# DS18B20_Modbus_v0_1.net
KiCad netlist of a schematic drawn in EAGLE
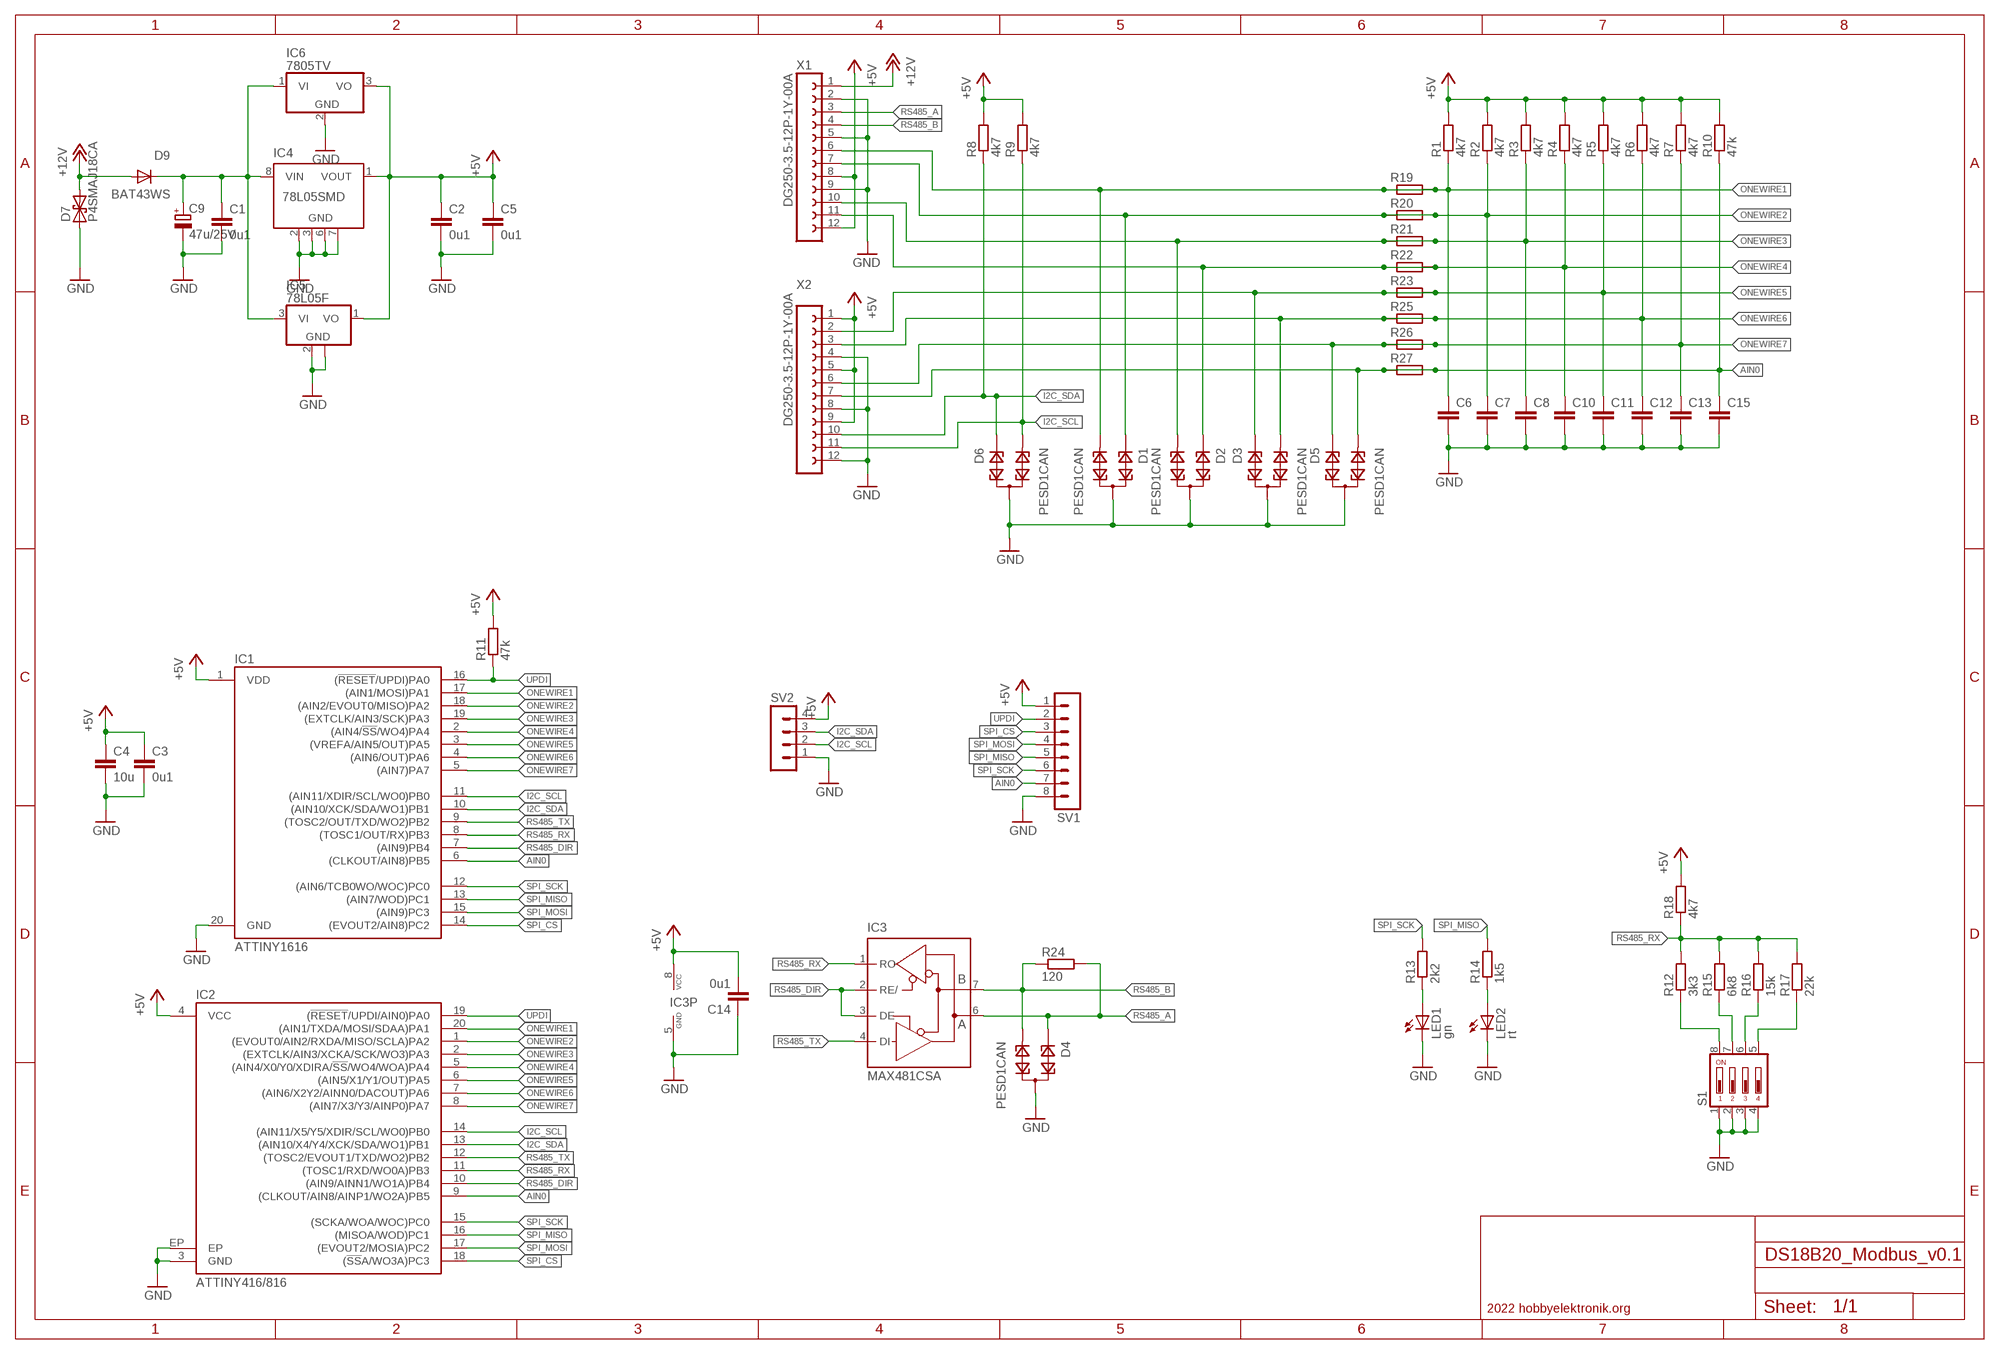
[diagram p0: schematic, sheet 1]

(export (version "E")
  (design (tool "Eeschema 10.0.6"))
  (components
    (comp (ref "C1")
      (value "0u1")
      (footprint "eagle-import:C0805")
      (libsource (lib "eagle-import") (part "C-EUC0805"))
    )
    (comp (ref "C2")
      (value "0u1")
      (footprint "eagle-import:C0603")
      (libsource (lib "eagle-import") (part "C-EUC0603"))
    )
    (comp (ref "C3")
      (value "0u1")
      (footprint "eagle-import:C0603")
      (libsource (lib "eagle-import") (part "C-EUC0603"))
    )
    (comp (ref "C4")
      (value "10u")
      (footprint "eagle-import:C0805")
      (libsource (lib "eagle-import") (part "C-EUC0805"))
    )
    (comp (ref "C5")
      (value "0u1")
      (footprint "eagle-import:C0603")
      (libsource (lib "eagle-import") (part "C-EUC0603"))
    )
    (comp (ref "C6")
      (value "C-EUC0603")
      (footprint "eagle-import:C0603")
      (libsource (lib "eagle-import") (part "C-EUC0603"))
    )
    (comp (ref "C7")
      (value "C-EUC0603")
      (footprint "eagle-import:C0603")
      (libsource (lib "eagle-import") (part "C-EUC0603"))
    )
    (comp (ref "C8")
      (value "C-EUC0603")
      (footprint "eagle-import:C0603")
      (libsource (lib "eagle-import") (part "C-EUC0603"))
    )
    (comp (ref "C9")
      (value "47u/25V")
      (footprint "eagle-import:E2,5-5")
      (libsource (lib "eagle-import") (part "CPOL-EUE2.5-5"))
    )
    (comp (ref "C10")
      (value "C-EUC0603")
      (footprint "eagle-import:C0603")
      (libsource (lib "eagle-import") (part "C-EUC0603"))
    )
    (comp (ref "C11")
      (value "C-EUC0603")
      (footprint "eagle-import:C0603")
      (libsource (lib "eagle-import") (part "C-EUC0603"))
    )
    (comp (ref "C12")
      (value "C-EUC0603")
      (footprint "eagle-import:C0603")
      (libsource (lib "eagle-import") (part "C-EUC0603"))
    )
    (comp (ref "C13")
      (value "C-EUC0603")
      (footprint "eagle-import:C0603")
      (libsource (lib "eagle-import") (part "C-EUC0603"))
    )
    (comp (ref "C14")
      (value "0u1")
      (footprint "eagle-import:C0603")
      (libsource (lib "eagle-import") (part "C-EUC0603"))
    )
    (comp (ref "C15")
      (value "C-EUC0603")
      (footprint "eagle-import:C0603")
      (libsource (lib "eagle-import") (part "C-EUC0603"))
    )
    (comp (ref "D1")
      (value "PESD1CAN")
      (footprint "eagle-import:SOT23")
      (libsource (lib "eagle-import") (part "PESD1CAN"))
    )
    (comp (ref "D2")
      (value "PESD1CAN")
      (footprint "eagle-import:SOT23")
      (libsource (lib "eagle-import") (part "PESD1CAN"))
    )
    (comp (ref "D3")
      (value "PESD1CAN")
      (footprint "eagle-import:SOT23")
      (libsource (lib "eagle-import") (part "PESD1CAN"))
    )
    (comp (ref "D4")
      (value "PESD1CAN")
      (footprint "eagle-import:SOT23")
      (libsource (lib "eagle-import") (part "PESD1CAN"))
    )
    (comp (ref "D5")
      (value "PESD1CAN")
      (footprint "eagle-import:SOT23")
      (libsource (lib "eagle-import") (part "PESD1CAN"))
    )
    (comp (ref "D6")
      (value "PESD1CAN")
      (footprint "eagle-import:SOT23")
      (libsource (lib "eagle-import") (part "PESD1CAN"))
    )
    (comp (ref "D7")
      (value "P4SMAJ18CA")
      (footprint "eagle-import:DO214AC")
      (fields (field (name "OC_REICHELT") "P4SMAJ18CA"))
      (libsource (lib "eagle-import") (part "P4SMAJ10CA"))
    )
    (comp (ref "D9")
      (value "BAT43WS")
      (footprint "eagle-import:SOD323-W")
      (libsource (lib "eagle-import") (part "DIODE-SOD323-W"))
    )
    (comp (ref "IC1")
      (value "ATTINY1616")
      (footprint "eagle-import:SO20_T1616")
      (libsource (lib "eagle-import") (part "ATTINY1616"))
    )
    (comp (ref "IC2")
      (value "ATTINY416/816")
      (footprint "eagle-import:ZCL_VQFN-20")
      (libsource (lib "eagle-import") (part "ATTINY416/816"))
    )
    (comp (ref "IC3")
      (value "MAX481CSA")
      (footprint "eagle-import:SO08")
      (fields (field (name "MF") "MAXIM") (field (name "OC_REICHELT") "MAX 481 CSA"))
      (libsource (lib "eagle-import") (part "MAX481CSA"))
    )
    (comp (ref "IC4")
      (value "78L05SMD")
      (footprint "eagle-import:SO08")
      (libsource (lib "eagle-import") (part "78LSMD05"))
    )
    (comp (ref "IC5")
      (value "78L05F")
      (footprint "eagle-import:SOT89")
      (libsource (lib "eagle-import") (part "78LF05"))
    )
    (comp (ref "IC6")
      (value "7805TV")
      (footprint "eagle-import:TO220V")
      (libsource (lib "eagle-import") (part "78TV05"))
    )
    (comp (ref "LED1")
      (value "gn")
      (footprint "eagle-import:SML0805")
      (libsource (lib "eagle-import") (part "LEDSML0805"))
    )
    (comp (ref "LED2")
      (value "rt")
      (footprint "eagle-import:SML0805")
      (libsource (lib "eagle-import") (part "LEDSML0805"))
    )
    (comp (ref "R1")
      (value "4k7")
      (footprint "eagle-import:R0603")
      (libsource (lib "eagle-import") (part "R-EU_R0603"))
    )
    (comp (ref "R2")
      (value "4k7")
      (footprint "eagle-import:R0603")
      (libsource (lib "eagle-import") (part "R-EU_R0603"))
    )
    (comp (ref "R3")
      (value "4k7")
      (footprint "eagle-import:R0603")
      (libsource (lib "eagle-import") (part "R-EU_R0603"))
    )
    (comp (ref "R4")
      (value "4k7")
      (footprint "eagle-import:R0603")
      (libsource (lib "eagle-import") (part "R-EU_R0603"))
    )
    (comp (ref "R5")
      (value "4k7")
      (footprint "eagle-import:R0603")
      (libsource (lib "eagle-import") (part "R-EU_R0603"))
    )
    (comp (ref "R6")
      (value "4k7")
      (footprint "eagle-import:R0603")
      (libsource (lib "eagle-import") (part "R-EU_R0603"))
    )
    (comp (ref "R7")
      (value "4k7")
      (footprint "eagle-import:R0603")
      (libsource (lib "eagle-import") (part "R-EU_R0603"))
    )
    (comp (ref "R8")
      (value "4k7")
      (footprint "eagle-import:R0603")
      (libsource (lib "eagle-import") (part "R-EU_R0603"))
    )
    (comp (ref "R9")
      (value "4k7")
      (footprint "eagle-import:R0603")
      (libsource (lib "eagle-import") (part "R-EU_R0603"))
    )
    (comp (ref "R10")
      (value "47k")
      (footprint "eagle-import:R0603")
      (libsource (lib "eagle-import") (part "R-EU_R0603"))
    )
    (comp (ref "R11")
      (value "47k")
      (footprint "eagle-import:R0603")
      (libsource (lib "eagle-import") (part "R-EU_R0603"))
    )
    (comp (ref "R12")
      (value "3k3")
      (footprint "eagle-import:R0603")
      (libsource (lib "eagle-import") (part "R-EU_R0603"))
    )
    (comp (ref "R13")
      (value "2k2")
      (footprint "eagle-import:R0603")
      (libsource (lib "eagle-import") (part "R-EU_R0603"))
    )
    (comp (ref "R14")
      (value "1k5")
      (footprint "eagle-import:R0603")
      (libsource (lib "eagle-import") (part "R-EU_R0603"))
    )
    (comp (ref "R15")
      (value "6k8")
      (footprint "eagle-import:R0603")
      (libsource (lib "eagle-import") (part "R-EU_R0603"))
    )
    (comp (ref "R16")
      (value "15k")
      (footprint "eagle-import:R0603")
      (libsource (lib "eagle-import") (part "R-EU_R0603"))
    )
    (comp (ref "R17")
      (value "22k")
      (footprint "eagle-import:R0603")
      (libsource (lib "eagle-import") (part "R-EU_R0603"))
    )
    (comp (ref "R18")
      (value "4k7")
      (footprint "eagle-import:R0603")
      (libsource (lib "eagle-import") (part "R-EU_R0603"))
    )
    (comp (ref "R19")
      (value "R-EU_R0603")
      (footprint "eagle-import:R0603")
      (libsource (lib "eagle-import") (part "R-EU_R0603"))
    )
    (comp (ref "R20")
      (value "R-EU_R0603")
      (footprint "eagle-import:R0603")
      (libsource (lib "eagle-import") (part "R-EU_R0603"))
    )
    (comp (ref "R21")
      (value "R-EU_R0603")
      (footprint "eagle-import:R0603")
      (libsource (lib "eagle-import") (part "R-EU_R0603"))
    )
    (comp (ref "R22")
      (value "R-EU_R0603")
      (footprint "eagle-import:R0603")
      (libsource (lib "eagle-import") (part "R-EU_R0603"))
    )
    (comp (ref "R23")
      (value "R-EU_R0603")
      (footprint "eagle-import:R0603")
      (libsource (lib "eagle-import") (part "R-EU_R0603"))
    )
    (comp (ref "R24")
      (value "120")
      (footprint "eagle-import:R0603")
      (libsource (lib "eagle-import") (part "R-EU_R0603"))
    )
    (comp (ref "R25")
      (value "R-EU_R0603")
      (footprint "eagle-import:R0603")
      (libsource (lib "eagle-import") (part "R-EU_R0603"))
    )
    (comp (ref "R26")
      (value "R-EU_R0603")
      (footprint "eagle-import:R0603")
      (libsource (lib "eagle-import") (part "R-EU_R0603"))
    )
    (comp (ref "R27")
      (value "R-EU_R0603")
      (footprint "eagle-import:R0603")
      (libsource (lib "eagle-import") (part "R-EU_R0603"))
    )
    (comp (ref "S1")
      (value "DS04")
      (footprint "eagle-import:DS-04")
      (libsource (lib "eagle-import") (part "DS04"))
    )
    (comp (ref "SV1")
      (value "MA08-1R")
      (footprint "eagle-import:MA08-1R")
      (libsource (lib "eagle-import") (part "MA08-1R"))
    )
    (comp (ref "SV2")
      (value "MA04-1R")
      (footprint "eagle-import:MA04-1R")
      (libsource (lib "eagle-import") (part "MA04-1R"))
    )
    (comp (ref "X1")
      (value "DG250-3.5-12P-1Y-00A")
      (footprint "eagle-import:DG250-3.5-12P-1Y-00A")
      (libsource (lib "eagle-import") (part "DG250-3.5-12P-1Y-00A"))
    )
    (comp (ref "X2")
      (value "DG250-3.5-12P-1Y-00A")
      (footprint "eagle-import:DG250-3.5-12P-1Y-00A")
      (libsource (lib "eagle-import") (part "DG250-3.5-12P-1Y-00A"))
    )
  )
  (nets
    (net (code "1") (name "+5V") (class "Default")
      (node (ref "C14") (pin "2") (pinfunction "2_2") (pintype "passive"))
      (node (ref "C2") (pin "1") (pinfunction "1_1") (pintype "passive"))
      (node (ref "C3") (pin "1") (pinfunction "1_1") (pintype "passive"))
      (node (ref "C4") (pin "1") (pinfunction "1_1") (pintype "passive"))
      (node (ref "C5") (pin "1") (pinfunction "1_1") (pintype "passive"))
      (node (ref "IC1") (pin "1") (pinfunction "VDD_1") (pintype "power_in"))
      (node (ref "IC2") (pin "4") (pinfunction "VCC_4") (pintype "power_in"))
      (node (ref "IC3") (pin "8") (pinfunction "VCC_8") (pintype "power_in"))
      (node (ref "IC4") (pin "1") (pinfunction "VOUT_1") (pintype "output"))
      (node (ref "IC5") (pin "1") (pinfunction "VO_1") (pintype "passive"))
      (node (ref "IC6") (pin "3") (pinfunction "VO_3") (pintype "passive"))
      (node (ref "R1") (pin "2") (pinfunction "2_2") (pintype "passive"))
      (node (ref "R10") (pin "2") (pinfunction "2_2") (pintype "passive"))
      (node (ref "R11") (pin "2") (pinfunction "2_2") (pintype "passive"))
      (node (ref "R18") (pin "2") (pinfunction "2_2") (pintype "passive"))
      (node (ref "R2") (pin "2") (pinfunction "2_2") (pintype "passive"))
      (node (ref "R3") (pin "2") (pinfunction "2_2") (pintype "passive"))
      (node (ref "R4") (pin "2") (pinfunction "2_2") (pintype "passive"))
      (node (ref "R5") (pin "2") (pinfunction "2_2") (pintype "passive"))
      (node (ref "R6") (pin "2") (pinfunction "2_2") (pintype "passive"))
      (node (ref "R7") (pin "2") (pinfunction "2_2") (pintype "passive"))
      (node (ref "R8") (pin "2") (pinfunction "2_2") (pintype "passive"))
      (node (ref "R9") (pin "2") (pinfunction "2_2") (pintype "passive"))
      (node (ref "SV1") (pin "1") (pinfunction "1_1") (pintype "passive"))
      (node (ref "SV2") (pin "4") (pinfunction "4_4") (pintype "passive"))
      (node (ref "X1") (pin "12") (pinfunction "12_12") (pintype "passive"))
      (node (ref "X1") (pin "8") (pinfunction "8_8") (pintype "passive"))
      (node (ref "X2") (pin "1") (pinfunction "1_1") (pintype "passive"))
      (node (ref "X2") (pin "5") (pinfunction "5_5") (pintype "passive"))
      (node (ref "X2") (pin "9") (pinfunction "9_9") (pintype "passive"))
    )
    (net (code "2") (name "+12V") (class "Default")
      (node (ref "D7") (pin "2") (pinfunction "2_2") (pintype "passive"))
      (node (ref "D9") (pin "A") (pinfunction "A_A") (pintype "passive"))
      (node (ref "X1") (pin "1") (pinfunction "1_1") (pintype "passive"))
    )
    (net (code "3") (name "AIN0") (class "Default")
      (node (ref "C15") (pin "1") (pinfunction "1_1") (pintype "passive"))
      (node (ref "D5") (pin "2") (pinfunction "2_2") (pintype "passive"))
      (node (ref "IC1") (pin "6") (pinfunction "(CLKOUT/AIN8)PB5_6") (pintype "bidirectional"))
      (node (ref "IC2") (pin "9") (pinfunction "(CLKOUT/AIN8/AINP1/WO2A)PB5_9") (pintype "bidirectional"))
      (node (ref "R10") (pin "1") (pinfunction "1_1") (pintype "passive"))
      (node (ref "R27") (pin "1") (pinfunction "1_1") (pintype "passive"))
      (node (ref "R27") (pin "2") (pinfunction "2_2") (pintype "passive"))
      (node (ref "SV1") (pin "7") (pinfunction "7_7") (pintype "passive"))
      (node (ref "X2") (pin "7") (pinfunction "7_7") (pintype "passive"))
    )
    (net (code "4") (name "GND") (class "Default")
      (node (ref "C1") (pin "2") (pinfunction "2_2") (pintype "passive"))
      (node (ref "C10") (pin "2") (pinfunction "2_2") (pintype "passive"))
      (node (ref "C11") (pin "2") (pinfunction "2_2") (pintype "passive"))
      (node (ref "C12") (pin "2") (pinfunction "2_2") (pintype "passive"))
      (node (ref "C13") (pin "2") (pinfunction "2_2") (pintype "passive"))
      (node (ref "C14") (pin "1") (pinfunction "1_1") (pintype "passive"))
      (node (ref "C15") (pin "2") (pinfunction "2_2") (pintype "passive"))
      (node (ref "C2") (pin "2") (pinfunction "2_2") (pintype "passive"))
      (node (ref "C3") (pin "2") (pinfunction "2_2") (pintype "passive"))
      (node (ref "C4") (pin "2") (pinfunction "2_2") (pintype "passive"))
      (node (ref "C5") (pin "2") (pinfunction "2_2") (pintype "passive"))
      (node (ref "C6") (pin "2") (pinfunction "2_2") (pintype "passive"))
      (node (ref "C7") (pin "2") (pinfunction "2_2") (pintype "passive"))
      (node (ref "C8") (pin "2") (pinfunction "2_2") (pintype "passive"))
      (node (ref "C9") (pin "-") (pinfunction "-_-") (pintype "passive"))
      (node (ref "D1") (pin "3") (pinfunction "3_3") (pintype "passive"))
      (node (ref "D2") (pin "3") (pinfunction "3_3") (pintype "passive"))
      (node (ref "D3") (pin "3") (pinfunction "3_3") (pintype "passive"))
      (node (ref "D4") (pin "3") (pinfunction "3_3") (pintype "passive"))
      (node (ref "D5") (pin "3") (pinfunction "3_3") (pintype "passive"))
      (node (ref "D6") (pin "3") (pinfunction "3_3") (pintype "passive"))
      (node (ref "D7") (pin "1") (pinfunction "1_1") (pintype "passive"))
      (node (ref "IC1") (pin "20") (pinfunction "GND_20") (pintype "power_in"))
      (node (ref "IC2") (pin "3") (pinfunction "GND_3") (pintype "power_in"))
      (node (ref "IC2") (pin "EP") (pinfunction "EP_EP") (pintype "power_in"))
      (node (ref "IC3") (pin "5") (pinfunction "GND_5") (pintype "power_in"))
      (node (ref "IC4") (pin "2") (pinfunction "GND_2") (pintype "power_in"))
      (node (ref "IC4") (pin "3") (pinfunction "GND_3") (pintype "power_in"))
      (node (ref "IC4") (pin "6") (pinfunction "GND_6") (pintype "power_in"))
      (node (ref "IC4") (pin "7") (pinfunction "GND_7") (pintype "power_in"))
      (node (ref "IC5") (pin "2") (pinfunction "GND_2") (pintype "passive"))
      (node (ref "IC5") (pin "2@1") (pinfunction "GND_2@1") (pintype "passive"))
      (node (ref "IC6") (pin "2") (pinfunction "GND_2") (pintype "passive"))
      (node (ref "LED1") (pin "C") (pinfunction "C_C") (pintype "passive"))
      (node (ref "LED2") (pin "C") (pinfunction "C_C") (pintype "passive"))
      (node (ref "S1") (pin "1") (pinfunction "1_1") (pintype "passive"))
      (node (ref "S1") (pin "2") (pinfunction "2_2") (pintype "passive"))
      (node (ref "S1") (pin "3") (pinfunction "3_3") (pintype "passive"))
      (node (ref "S1") (pin "4") (pinfunction "4_4") (pintype "passive"))
      (node (ref "SV1") (pin "8") (pinfunction "8_8") (pintype "passive"))
      (node (ref "SV2") (pin "1") (pinfunction "1_1") (pintype "passive"))
      (node (ref "X1") (pin "2") (pinfunction "2_2") (pintype "passive"))
      (node (ref "X1") (pin "5") (pinfunction "5_5") (pintype "passive"))
      (node (ref "X1") (pin "9") (pinfunction "9_9") (pintype "passive"))
      (node (ref "X2") (pin "12") (pinfunction "12_12") (pintype "passive"))
      (node (ref "X2") (pin "4") (pinfunction "4_4") (pintype "passive"))
      (node (ref "X2") (pin "8") (pinfunction "8_8") (pintype "passive"))
    )
    (net (code "5") (name "I2C_SCL") (class "Default")
      (node (ref "D6") (pin "2") (pinfunction "2_2") (pintype "passive"))
      (node (ref "IC1") (pin "11") (pinfunction "(AIN11/XDIR/SCL/WO0)PB0_11") (pintype "bidirectional"))
      (node (ref "IC2") (pin "14") (pinfunction "(AIN11/X5/Y5/XDIR/SCL/WO0)PB0_14") (pintype "bidirectional"))
      (node (ref "R9") (pin "1") (pinfunction "1_1") (pintype "passive"))
      (node (ref "SV2") (pin "2") (pinfunction "2_2") (pintype "passive"))
      (node (ref "X2") (pin "11") (pinfunction "11_11") (pintype "passive"))
    )
    (net (code "6") (name "I2C_SDA") (class "Default")
      (node (ref "D6") (pin "1") (pinfunction "1_1") (pintype "passive"))
      (node (ref "IC1") (pin "10") (pinfunction "(AIN10/XCK/SDA/WO1)PB1_10") (pintype "bidirectional"))
      (node (ref "IC2") (pin "13") (pinfunction "(AIN10/X4/Y4/XCK/SDA/WO1)PB1_13") (pintype "bidirectional"))
      (node (ref "R8") (pin "1") (pinfunction "1_1") (pintype "passive"))
      (node (ref "SV2") (pin "3") (pinfunction "3_3") (pintype "passive"))
      (node (ref "X2") (pin "10") (pinfunction "10_10") (pintype "passive"))
    )
    (net (code "7") (name "Net-(IC4A-VIN)") (class "Default")
      (node (ref "C1") (pin "1") (pinfunction "1_1") (pintype "passive"))
      (node (ref "C9") (pin "+") (pinfunction "+_+") (pintype "passive"))
      (node (ref "D9") (pin "C") (pinfunction "C_C") (pintype "passive"))
      (node (ref "IC4") (pin "8") (pinfunction "VIN_8") (pintype "passive"))
      (node (ref "IC5") (pin "3") (pinfunction "VI_3") (pintype "input"))
      (node (ref "IC6") (pin "1") (pinfunction "VI_1") (pintype "input"))
    )
    (net (code "8") (name "Net-(LED1-PadA)") (class "Default")
      (node (ref "LED1") (pin "A") (pinfunction "A_A") (pintype "passive"))
      (node (ref "R13") (pin "1") (pinfunction "1_1") (pintype "passive"))
    )
    (net (code "9") (name "Net-(LED2-PadA)") (class "Default")
      (node (ref "LED2") (pin "A") (pinfunction "A_A") (pintype "passive"))
      (node (ref "R14") (pin "1") (pinfunction "1_1") (pintype "passive"))
    )
    (net (code "10") (name "Net-(R12-Pad1)") (class "Default")
      (node (ref "R12") (pin "1") (pinfunction "1_1") (pintype "passive"))
      (node (ref "S1") (pin "8") (pinfunction "8_8") (pintype "passive"))
    )
    (net (code "11") (name "Net-(R15-Pad1)") (class "Default")
      (node (ref "R15") (pin "1") (pinfunction "1_1") (pintype "passive"))
      (node (ref "S1") (pin "7") (pinfunction "7_7") (pintype "passive"))
    )
    (net (code "12") (name "Net-(R16-Pad1)") (class "Default")
      (node (ref "R16") (pin "1") (pinfunction "1_1") (pintype "passive"))
      (node (ref "S1") (pin "6") (pinfunction "6_6") (pintype "passive"))
    )
    (net (code "13") (name "Net-(R17-Pad1)") (class "Default")
      (node (ref "R17") (pin "1") (pinfunction "1_1") (pintype "passive"))
      (node (ref "S1") (pin "5") (pinfunction "5_5") (pintype "passive"))
    )
    (net (code "14") (name "ONEWIRE1") (class "Default")
      (node (ref "C6") (pin "1") (pinfunction "1_1") (pintype "passive"))
      (node (ref "D1") (pin "2") (pinfunction "2_2") (pintype "passive"))
      (node (ref "IC1") (pin "17") (pinfunction "(AIN1/MOSI)PA1_17") (pintype "bidirectional"))
      (node (ref "IC2") (pin "20") (pinfunction "(AIN1/TXDA/MOSI/SDAA)PA1_20") (pintype "bidirectional"))
      (node (ref "R1") (pin "1") (pinfunction "1_1") (pintype "passive"))
      (node (ref "R19") (pin "1") (pinfunction "1_1") (pintype "passive"))
      (node (ref "R19") (pin "2") (pinfunction "2_2") (pintype "passive"))
      (node (ref "X1") (pin "6") (pinfunction "6_6") (pintype "passive"))
    )
    (net (code "15") (name "ONEWIRE2") (class "Default")
      (node (ref "C7") (pin "1") (pinfunction "1_1") (pintype "passive"))
      (node (ref "D1") (pin "1") (pinfunction "1_1") (pintype "passive"))
      (node (ref "IC1") (pin "18") (pinfunction "(AIN2/EVOUT0/MISO)PA2_18") (pintype "bidirectional"))
      (node (ref "IC2") (pin "1") (pinfunction "(EVOUT0/AIN2/RXDA/MISO/SCLA)PA2_1") (pintype "bidirectional"))
      (node (ref "R2") (pin "1") (pinfunction "1_1") (pintype "passive"))
      (node (ref "R20") (pin "1") (pinfunction "1_1") (pintype "passive"))
      (node (ref "R20") (pin "2") (pinfunction "2_2") (pintype "passive"))
      (node (ref "X1") (pin "7") (pinfunction "7_7") (pintype "passive"))
    )
    (net (code "16") (name "ONEWIRE3") (class "Default")
      (node (ref "C8") (pin "1") (pinfunction "1_1") (pintype "passive"))
      (node (ref "D2") (pin "2") (pinfunction "2_2") (pintype "passive"))
      (node (ref "IC1") (pin "19") (pinfunction "(EXTCLK/AIN3/SCK)PA3_19") (pintype "bidirectional"))
      (node (ref "IC2") (pin "2") (pinfunction "(EXTCLK/AIN3/XCKA/SCK/WO3)PA3_2") (pintype "bidirectional"))
      (node (ref "R21") (pin "1") (pinfunction "1_1") (pintype "passive"))
      (node (ref "R21") (pin "2") (pinfunction "2_2") (pintype "passive"))
      (node (ref "R3") (pin "1") (pinfunction "1_1") (pintype "passive"))
      (node (ref "X1") (pin "10") (pinfunction "10_10") (pintype "passive"))
    )
    (net (code "17") (name "ONEWIRE4") (class "Default")
      (node (ref "C10") (pin "1") (pinfunction "1_1") (pintype "passive"))
      (node (ref "D2") (pin "1") (pinfunction "1_1") (pintype "passive"))
      (node (ref "IC1") (pin "2") (pinfunction "(AIN4/~{SS}/WO4)PA4_2") (pintype "bidirectional"))
      (node (ref "IC2") (pin "5") (pinfunction "(AIN4/X0/Y0/XDIRA/~{SS}/WO4/WOA)PA4_5") (pintype "bidirectional"))
      (node (ref "R22") (pin "1") (pinfunction "1_1") (pintype "passive"))
      (node (ref "R22") (pin "2") (pinfunction "2_2") (pintype "passive"))
      (node (ref "R4") (pin "1") (pinfunction "1_1") (pintype "passive"))
      (node (ref "X1") (pin "11") (pinfunction "11_11") (pintype "passive"))
    )
    (net (code "18") (name "ONEWIRE5") (class "Default")
      (node (ref "C11") (pin "1") (pinfunction "1_1") (pintype "passive"))
      (node (ref "D3") (pin "1") (pinfunction "1_1") (pintype "passive"))
      (node (ref "IC1") (pin "3") (pinfunction "(VREFA/AIN5/OUT)PA5_3") (pintype "bidirectional"))
      (node (ref "IC2") (pin "6") (pinfunction "(AIN5/X1/Y1/OUT)PA5_6") (pintype "bidirectional"))
      (node (ref "R23") (pin "1") (pinfunction "1_1") (pintype "passive"))
      (node (ref "R23") (pin "2") (pinfunction "2_2") (pintype "passive"))
      (node (ref "R5") (pin "1") (pinfunction "1_1") (pintype "passive"))
      (node (ref "X2") (pin "2") (pinfunction "2_2") (pintype "passive"))
    )
    (net (code "19") (name "ONEWIRE6") (class "Default")
      (node (ref "C12") (pin "1") (pinfunction "1_1") (pintype "passive"))
      (node (ref "D3") (pin "2") (pinfunction "2_2") (pintype "passive"))
      (node (ref "IC1") (pin "4") (pinfunction "(AIN6/OUT)PA6_4") (pintype "bidirectional"))
      (node (ref "IC2") (pin "7") (pinfunction "(AIN6/X2Y2/AINN0/DACOUT)PA6_7") (pintype "bidirectional"))
      (node (ref "R25") (pin "1") (pinfunction "1_1") (pintype "passive"))
      (node (ref "R25") (pin "2") (pinfunction "2_2") (pintype "passive"))
      (node (ref "R6") (pin "1") (pinfunction "1_1") (pintype "passive"))
      (node (ref "X2") (pin "3") (pinfunction "3_3") (pintype "passive"))
    )
    (net (code "20") (name "ONEWIRE7") (class "Default")
      (node (ref "C13") (pin "1") (pinfunction "1_1") (pintype "passive"))
      (node (ref "D5") (pin "1") (pinfunction "1_1") (pintype "passive"))
      (node (ref "IC1") (pin "5") (pinfunction "(AIN7)PA7_5") (pintype "bidirectional"))
      (node (ref "IC2") (pin "8") (pinfunction "(AIN7/X3/Y3/AINP0)PA7_8") (pintype "bidirectional"))
      (node (ref "R26") (pin "1") (pinfunction "1_1") (pintype "passive"))
      (node (ref "R26") (pin "2") (pinfunction "2_2") (pintype "passive"))
      (node (ref "R7") (pin "1") (pinfunction "1_1") (pintype "passive"))
      (node (ref "X2") (pin "6") (pinfunction "6_6") (pintype "passive"))
    )
    (net (code "21") (name "RS485_A") (class "Default")
      (node (ref "D4") (pin "1") (pinfunction "1_1") (pintype "passive"))
      (node (ref "IC3") (pin "6") (pinfunction "A_6") (pintype "passive"))
      (node (ref "R24") (pin "2") (pinfunction "2_2") (pintype "passive"))
      (node (ref "X1") (pin "3") (pinfunction "3_3") (pintype "passive"))
    )
    (net (code "22") (name "RS485_B") (class "Default")
      (node (ref "D4") (pin "2") (pinfunction "2_2") (pintype "passive"))
      (node (ref "IC3") (pin "7") (pinfunction "B_7") (pintype "passive"))
      (node (ref "R24") (pin "1") (pinfunction "1_1") (pintype "passive"))
      (node (ref "X1") (pin "4") (pinfunction "4_4") (pintype "passive"))
    )
    (net (code "23") (name "RS485_DIR") (class "Default")
      (node (ref "IC1") (pin "7") (pinfunction "(AIN9)PB4_7") (pintype "bidirectional"))
      (node (ref "IC2") (pin "10") (pinfunction "(AIN9/AINN1/WO1A)PB4_10") (pintype "bidirectional"))
      (node (ref "IC3") (pin "2") (pinfunction "RE/_2") (pintype "input"))
      (node (ref "IC3") (pin "3") (pinfunction "DE_3") (pintype "input"))
    )
    (net (code "24") (name "RS485_RX") (class "Default")
      (node (ref "IC1") (pin "8") (pinfunction "(TOSC1/OUT/RX)PB3_8") (pintype "bidirectional"))
      (node (ref "IC2") (pin "11") (pinfunction "(TOSC1/RXD/WO0A)PB3_11") (pintype "bidirectional"))
      (node (ref "IC3") (pin "1") (pinfunction "RO_1") (pintype "output"))
      (node (ref "R12") (pin "2") (pinfunction "2_2") (pintype "passive"))
      (node (ref "R15") (pin "2") (pinfunction "2_2") (pintype "passive"))
      (node (ref "R16") (pin "2") (pinfunction "2_2") (pintype "passive"))
      (node (ref "R17") (pin "2") (pinfunction "2_2") (pintype "passive"))
      (node (ref "R18") (pin "1") (pinfunction "1_1") (pintype "passive"))
    )
    (net (code "25") (name "RS485_TX") (class "Default")
      (node (ref "IC1") (pin "9") (pinfunction "(TOSC2/OUT/TXD/WO2)PB2_9") (pintype "bidirectional"))
      (node (ref "IC2") (pin "12") (pinfunction "(TOSC2/EVOUT1/TXD/WO2)PB2_12") (pintype "bidirectional"))
      (node (ref "IC3") (pin "4") (pinfunction "DI_4") (pintype "input"))
    )
    (net (code "26") (name "SPI_CS") (class "Default")
      (node (ref "IC1") (pin "14") (pinfunction "(EVOUT2/AIN8)PC2_14") (pintype "bidirectional"))
      (node (ref "IC2") (pin "18") (pinfunction "(~{SS}A/WO3A)PC3_18") (pintype "bidirectional"))
      (node (ref "SV1") (pin "3") (pinfunction "3_3") (pintype "passive"))
    )
    (net (code "27") (name "SPI_MISO") (class "Default")
      (node (ref "IC1") (pin "13") (pinfunction "(AIN7/WOD)PC1_13") (pintype "bidirectional"))
      (node (ref "IC2") (pin "16") (pinfunction "(MISOA/WOD)PC1_16") (pintype "bidirectional"))
      (node (ref "R14") (pin "2") (pinfunction "2_2") (pintype "passive"))
      (node (ref "SV1") (pin "5") (pinfunction "5_5") (pintype "passive"))
    )
    (net (code "28") (name "SPI_MOSI") (class "Default")
      (node (ref "IC1") (pin "15") (pinfunction "(AIN9)PC3_15") (pintype "bidirectional"))
      (node (ref "IC2") (pin "17") (pinfunction "(EVOUT2/MOSIA)PC2_17") (pintype "bidirectional"))
      (node (ref "SV1") (pin "4") (pinfunction "4_4") (pintype "passive"))
    )
    (net (code "29") (name "SPI_SCK") (class "Default")
      (node (ref "IC1") (pin "12") (pinfunction "(AIN6/TCB0WO/WOC)PC0_12") (pintype "bidirectional"))
      (node (ref "IC2") (pin "15") (pinfunction "(SCKA/WOA/WOC)PC0_15") (pintype "bidirectional"))
      (node (ref "R13") (pin "2") (pinfunction "2_2") (pintype "passive"))
      (node (ref "SV1") (pin "6") (pinfunction "6_6") (pintype "passive"))
    )
    (net (code "30") (name "UPDI") (class "Default")
      (node (ref "IC1") (pin "16") (pinfunction "(~{RESET}/UPDI)PA0_16") (pintype "bidirectional"))
      (node (ref "IC2") (pin "19") (pinfunction "(~{RESET}/UPDI/AIN0)PA0_19") (pintype "bidirectional"))
      (node (ref "R11") (pin "1") (pinfunction "1_1") (pintype "passive"))
      (node (ref "SV1") (pin "2") (pinfunction "2_2") (pintype "passive"))
    )
  )
)
